# Sheet1.net
KiCad netlist of a schematic drawn in Altium Designer
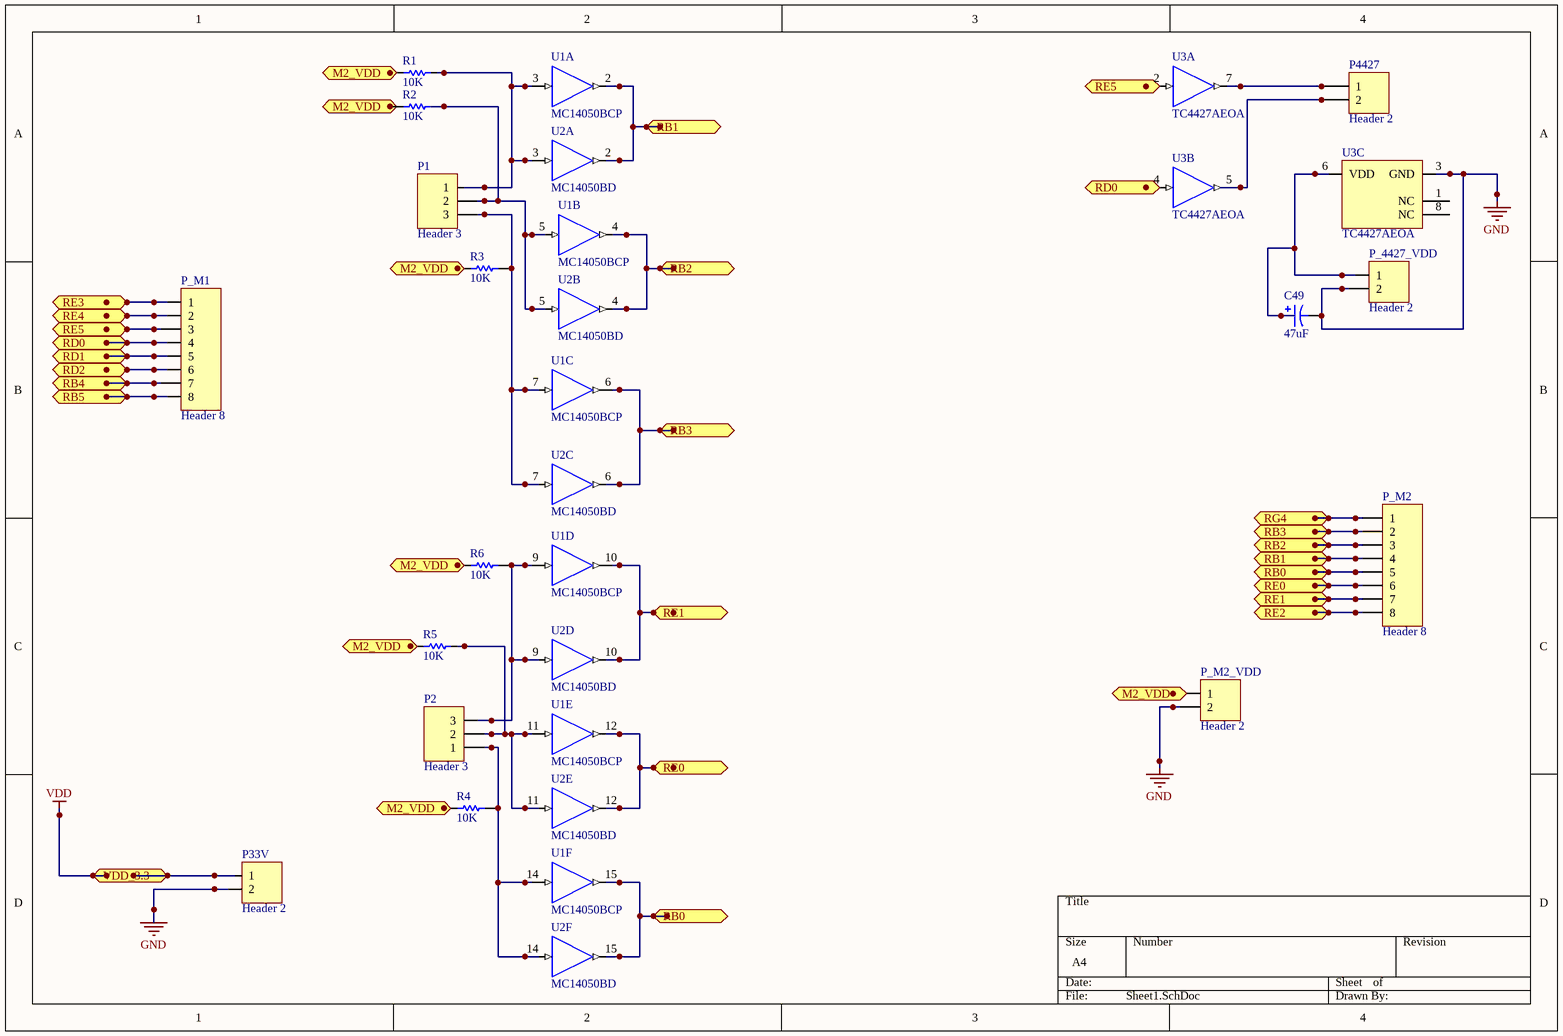
[diagram p0: Sheet1.SchDoc]

(export (version "E")
  (design (tool "Eeschema 10.0.6"))
  (components
    (comp (ref "C49")
      (value "47uF")
      (footprint "NSOALUMB")
      (description "Polarized Capacitor (Radial)")
      (fields (field (name "PUBLISHER") "Altium Limited"))
      (libsource (lib "Miscellaneous Devices") (part "Cap Pol1"))
    )
    (comp (ref "P1")
      (value "Header 3")
      (footprint "smd_cap:BIG3")
      (description "Header, 3-Pin")
      (fields (field (name "PUBLISHER") "Altium Limited"))
      (libsource (lib "Miscellaneous Connectors") (part "Header 3"))
    )
    (comp (ref "P2")
      (value "Header 3")
      (footprint "BIG3")
      (description "Header, 3-Pin")
      (fields (field (name "PUBLISHER") "Altium Limited"))
      (libsource (lib "") (part "Header 3_1"))
    )
    (comp (ref "P33V")
      (value "Header 2")
      (footprint "HDR1X2")
      (description "Header, 2-Pin")
      (fields (field (name "PUBLISHER") "Altium Limited"))
      (libsource (lib "Miscellaneous Connectors") (part "Header 2"))
    )
    (comp (ref "P4427")
      (value "Header 2")
      (footprint "BIG2")
      (description "Header, 2-Pin")
      (fields (field (name "PUBLISHER") "Altium Limited"))
      (libsource (lib "Miscellaneous Connectors") (part "Header 2"))
    )
    (comp (ref "P_4427_VDD")
      (value "Header 2")
      (footprint "BIG2")
      (description "Header, 2-Pin")
      (fields (field (name "PUBLISHER") "Altium Limited"))
      (libsource (lib "Miscellaneous Connectors") (part "Header 2"))
    )
    (comp (ref "P_M1")
      (value "Header 8")
      (footprint "HDR1X8")
      (description "Header, 8-Pin")
      (fields (field (name "PUBLISHER") "Altium Limited"))
      (libsource (lib "Miscellaneous Connectors") (part "Header 8"))
    )
    (comp (ref "P_M2")
      (value "Header 8")
      (footprint "HDR1X8")
      (description "Header, 8-Pin")
      (fields (field (name "PUBLISHER") "Altium Limited"))
      (libsource (lib "Miscellaneous Connectors") (part "Header 8"))
    )
    (comp (ref "P_M2_VDD")
      (value "Header 2")
      (footprint "BIG2")
      (description "Header, 2-Pin")
      (fields (field (name "PUBLISHER") "Altium Limited"))
      (libsource (lib "Miscellaneous Connectors") (part "Header 2"))
    )
    (comp (ref "R1")
      (value "10K")
      (footprint "RESC3216L")
      (description "Semiconductor Resistor")
      (fields (field (name "PUBLISHER") "Altium Limited"))
      (libsource (lib "Miscellaneous Devices") (part "Res Semi"))
    )
    (comp (ref "R2")
      (value "10K")
      (footprint "RESC3216L")
      (description "Semiconductor Resistor")
      (fields (field (name "PUBLISHER") "Altium Limited"))
      (libsource (lib "Miscellaneous Devices") (part "Res Semi"))
    )
    (comp (ref "R3")
      (value "10K")
      (footprint "RESC3216L")
      (description "Semiconductor Resistor")
      (fields (field (name "PUBLISHER") "Altium Limited"))
      (libsource (lib "Miscellaneous Devices") (part "Res Semi"))
    )
    (comp (ref "R4")
      (value "10K")
      (footprint "RESC3216L")
      (description "Semiconductor Resistor")
      (fields (field (name "PUBLISHER") "Altium Limited"))
      (libsource (lib "Miscellaneous Devices") (part "Res Semi"))
    )
    (comp (ref "R5")
      (value "10K")
      (footprint "RESC3216L")
      (description "Semiconductor Resistor")
      (fields (field (name "PUBLISHER") "Altium Limited"))
      (libsource (lib "Miscellaneous Devices") (part "Res Semi"))
    )
    (comp (ref "R6")
      (value "10K")
      (footprint "RESC3216L")
      (description "Semiconductor Resistor")
      (fields (field (name "PUBLISHER") "Altium Limited"))
      (libsource (lib "Miscellaneous Devices") (part "Res Semi"))
    )
    (comp (ref "U1")
      (value "MC14050BCP")
      (footprint "648-08")
      (description "Hex Non-Inverting Buffer")
      (fields (field (name "PUBLISHER") "Altium Limited"))
      (libsource (lib "ON Semi Logic Buffer Line Driver") (part "MC14050BCP"))
    )
    (comp (ref "U2")
      (value "MC14050BD")
      (footprint "751B-05_N")
      (description "Hex Non-Inverting Buffer")
      (fields (field (name "PUBLISHER") "Altium Limited"))
      (libsource (lib "ON Semi Logic Buffer Line Driver") (part "MC14050BD"))
    )
    (comp (ref "U3")
      (value "TC4427AEOA")
      (footprint "SOIC-OA8_N")
      (description "1.5A Dual High-Speed Power MOSFET Driver, Non-Inverting, Industrial Temperature")
      (fields (field (name "PUBLISHER") "Altium Limited"))
      (libsource (lib "Microchip Power Mgt MOSFET Driver") (part "TC4427AEOA"))
    )
  )
  (nets
    (net (code "2") (name "/RB0") (class "Default")
      (node (ref "P_M2") (pin "5") (pinfunction "5_5") (pintype "passive"))
      (node (ref "U1") (pin "15") (pinfunction "OUT_15") (pintype "output"))
      (node (ref "U2") (pin "15") (pinfunction "OUT_15") (pintype "output"))
    )
    (net (code "3") (name "/RB1") (class "Default")
      (node (ref "P_M2") (pin "4") (pinfunction "4_4") (pintype "passive"))
      (node (ref "U1") (pin "2") (pinfunction "OUT_2") (pintype "output"))
      (node (ref "U2") (pin "2") (pinfunction "OUT_2") (pintype "output"))
    )
    (net (code "4") (name "/RB2") (class "Default")
      (node (ref "P_M2") (pin "3") (pinfunction "3_3") (pintype "passive"))
      (node (ref "U1") (pin "4") (pinfunction "OUT_4") (pintype "output"))
      (node (ref "U2") (pin "4") (pinfunction "OUT_4") (pintype "output"))
    )
    (net (code "5") (name "/RB3") (class "Default")
      (node (ref "P_M2") (pin "2") (pinfunction "2_2") (pintype "passive"))
      (node (ref "U1") (pin "6") (pinfunction "OUT_6") (pintype "output"))
      (node (ref "U2") (pin "6") (pinfunction "OUT_6") (pintype "output"))
    )
    (net (code "6") (name "/RB4") (class "Default")
      (node (ref "P_M1") (pin "7") (pinfunction "7_7") (pintype "passive"))
    )
    (net (code "7") (name "/RB5") (class "Default")
      (node (ref "P_M1") (pin "8") (pinfunction "8_8") (pintype "passive"))
    )
    (net (code "8") (name "/RD0") (class "Default")
      (node (ref "P_M1") (pin "4") (pinfunction "4_4") (pintype "passive"))
    )
    (net (code "9") (name "/RD1") (class "Default")
      (node (ref "P_M1") (pin "5") (pinfunction "5_5") (pintype "passive"))
    )
    (net (code "10") (name "/RD2") (class "Default")
      (node (ref "P_M1") (pin "6") (pinfunction "6_6") (pintype "passive"))
    )
    (net (code "11") (name "/RE0") (class "Default")
      (node (ref "P_M2") (pin "6") (pinfunction "6_6") (pintype "passive"))
      (node (ref "U1") (pin "12") (pinfunction "OUT_12") (pintype "output"))
      (node (ref "U2") (pin "12") (pinfunction "OUT_12") (pintype "output"))
    )
    (net (code "12") (name "/RE1") (class "Default")
      (node (ref "P_M2") (pin "7") (pinfunction "7_7") (pintype "passive"))
      (node (ref "U1") (pin "10") (pinfunction "OUT_10") (pintype "output"))
      (node (ref "U2") (pin "10") (pinfunction "OUT_10") (pintype "output"))
    )
    (net (code "13") (name "/RE2") (class "Default")
      (node (ref "P_M2") (pin "8") (pinfunction "8_8") (pintype "passive"))
    )
    (net (code "14") (name "/RE3") (class "Default")
      (node (ref "P_M1") (pin "1") (pinfunction "1_1") (pintype "passive"))
    )
    (net (code "15") (name "/RE4") (class "Default")
      (node (ref "P_M1") (pin "2") (pinfunction "2_2") (pintype "passive"))
    )
    (net (code "16") (name "/RE5") (class "Default")
      (node (ref "P_M1") (pin "3") (pinfunction "3_3") (pintype "passive"))
    )
    (net (code "17") (name "/RG4") (class "Default")
      (node (ref "P_M2") (pin "1") (pinfunction "1_1") (pintype "passive"))
    )
    (net (code "18") (name "GND") (class "Default")
      (node (ref "C49") (pin "2") (pinfunction "2_2") (pintype "passive"))
      (node (ref "P33V") (pin "2") (pinfunction "2_2") (pintype "passive"))
      (node (ref "P_4427_VDD") (pin "2") (pinfunction "2_2") (pintype "passive"))
      (node (ref "P_M2_VDD") (pin "2") (pinfunction "2_2") (pintype "passive"))
      (node (ref "U1") (pin "8") (pinfunction "GND_8") (pintype "power_in"))
      (node (ref "U2") (pin "8") (pinfunction "GND_8") (pintype "power_in"))
      (node (ref "U3") (pin "3") (pinfunction "GND_3") (pintype "power_in"))
    )
    (net (code "19") (name "Net-(U1A-IN)") (class "Default")
      (node (ref "P1") (pin "1") (pinfunction "1_1") (pintype "passive"))
      (node (ref "R1") (pin "2") (pinfunction "2_2") (pintype "passive"))
      (node (ref "U1") (pin "3") (pinfunction "IN_3") (pintype "input"))
      (node (ref "U2") (pin "3") (pinfunction "IN_3") (pintype "input"))
    )
    (net (code "20") (name "Net-(U1B-IN)") (class "Default")
      (node (ref "P1") (pin "2") (pinfunction "2_2") (pintype "passive"))
      (node (ref "R2") (pin "2") (pinfunction "2_2") (pintype "passive"))
      (node (ref "U1") (pin "5") (pinfunction "IN_5") (pintype "input"))
      (node (ref "U2") (pin "5") (pinfunction "IN_5") (pintype "input"))
    )
    (net (code "21") (name "Net-(U1C-IN)") (class "Default")
      (node (ref "P1") (pin "3") (pinfunction "3_3") (pintype "passive"))
      (node (ref "R3") (pin "2") (pinfunction "2_2") (pintype "passive"))
      (node (ref "U1") (pin "7") (pinfunction "IN_7") (pintype "input"))
      (node (ref "U2") (pin "7") (pinfunction "IN_7") (pintype "input"))
    )
    (net (code "22") (name "Net-(U1D-IN)") (class "Default")
      (node (ref "P2") (pin "3") (pinfunction "3_3") (pintype "passive"))
      (node (ref "R6") (pin "2") (pinfunction "2_2") (pintype "passive"))
      (node (ref "U1") (pin "9") (pinfunction "IN_9") (pintype "input"))
      (node (ref "U2") (pin "9") (pinfunction "IN_9") (pintype "input"))
    )
    (net (code "23") (name "Net-(U1E-IN)") (class "Default")
      (node (ref "P2") (pin "2") (pinfunction "2_2") (pintype "passive"))
      (node (ref "R5") (pin "2") (pinfunction "2_2") (pintype "passive"))
      (node (ref "U1") (pin "11") (pinfunction "IN_11") (pintype "input"))
      (node (ref "U2") (pin "11") (pinfunction "IN_11") (pintype "input"))
    )
    (net (code "24") (name "Net-(U1F-IN)") (class "Default")
      (node (ref "P2") (pin "1") (pinfunction "1_1") (pintype "passive"))
      (node (ref "R4") (pin "2") (pinfunction "2_2") (pintype "passive"))
      (node (ref "U1") (pin "14") (pinfunction "IN_14") (pintype "input"))
      (node (ref "U2") (pin "14") (pinfunction "IN_14") (pintype "input"))
    )
    (net (code "25") (name "Net-(U3A-OUTA)") (class "Default")
      (node (ref "P4427") (pin "1") (pinfunction "1_1") (pintype "passive"))
      (node (ref "U3") (pin "7") (pinfunction "OUTA_7") (pintype "output"))
    )
    (net (code "26") (name "Net-(U3B-OUTB)") (class "Default")
      (node (ref "P4427") (pin "2") (pinfunction "2_2") (pintype "passive"))
      (node (ref "U3") (pin "5") (pinfunction "OUTB_5") (pintype "output"))
    )
    (net (code "27") (name "Net-(U3C-VDD)") (class "Default")
      (node (ref "C49") (pin "1") (pinfunction "1_1") (pintype "passive"))
      (node (ref "P_4427_VDD") (pin "1") (pinfunction "1_1") (pintype "passive"))
      (node (ref "U3") (pin "6") (pinfunction "VDD_6") (pintype "power_in"))
    )
    (net (code "28") (name "VDD") (class "Default")
      (node (ref "P33V") (pin "1") (pinfunction "1_1") (pintype "passive"))
      (node (ref "U1") (pin "1") (pinfunction "VDD_1") (pintype "power_in"))
      (node (ref "U2") (pin "1") (pinfunction "VDD_1") (pintype "power_in"))
    )
    (net (code "29") (name "unconnected-(P_M2_VDD-Pad1)") (class "Default")
      (node (ref "P_M2_VDD") (pin "1") (pinfunction "1_1") (pintype "passive"))
    )
    (net (code "30") (name "unconnected-(R1-Pad1)") (class "Default")
      (node (ref "R1") (pin "1") (pinfunction "1_1") (pintype "passive"))
    )
    (net (code "31") (name "unconnected-(R2-Pad1)") (class "Default")
      (node (ref "R2") (pin "1") (pinfunction "1_1") (pintype "passive"))
    )
    (net (code "32") (name "unconnected-(R3-Pad1)") (class "Default")
      (node (ref "R3") (pin "1") (pinfunction "1_1") (pintype "passive"))
    )
    (net (code "33") (name "unconnected-(R4-Pad1)") (class "Default")
      (node (ref "R4") (pin "1") (pinfunction "1_1") (pintype "passive"))
    )
    (net (code "34") (name "unconnected-(R5-Pad1)") (class "Default")
      (node (ref "R5") (pin "1") (pinfunction "1_1") (pintype "passive"))
    )
    (net (code "35") (name "unconnected-(R6-Pad1)") (class "Default")
      (node (ref "R6") (pin "1") (pinfunction "1_1") (pintype "passive"))
    )
    (net (code "36") (name "unconnected-(U3A-INA-Pad2)") (class "Default")
      (node (ref "U3") (pin "2") (pinfunction "INA_2") (pintype "input"))
    )
    (net (code "37") (name "unconnected-(U3B-INB-Pad4)") (class "Default")
      (node (ref "U3") (pin "4") (pinfunction "INB_4") (pintype "input"))
    )
    (net (code "38") (name "unconnected-(U3C-NC-Pad1)") (class "Default")
      (node (ref "U3") (pin "1") (pinfunction "NC_1") (pintype "passive"))
    )
    (net (code "39") (name "unconnected-(U3C-NC-Pad8)") (class "Default")
      (node (ref "U3") (pin "8") (pinfunction "NC_8") (pintype "passive"))
    )
  )
)
